# v1_5_GPS.net
KiCad netlist of a schematic drawn in Altium Designer
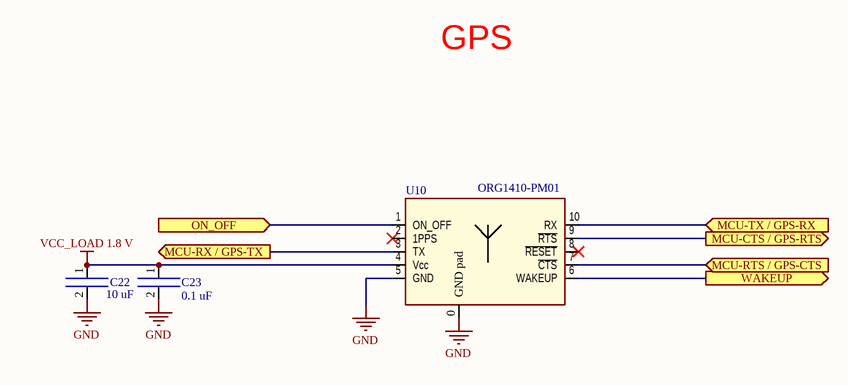
[diagram p0: v1.5 GPS.SchDoc]

(export (version "E")
  (design (tool "Eeschema 10.0.6"))
  (components
    (comp (ref "C22")
      (value "10 uF")
      (footprint "Ungravity Library:0603")
      (libsource (lib "Ungravity Library") (part "Capasistor"))
    )
    (comp (ref "C23")
      (value "0.1 uF")
      (footprint "Ungravity Library:0402")
      (libsource (lib "Ungravity Library") (part "Capasistor"))
    )
    (comp (ref "U10")
      (value "ORG1410-PM01")
      (footprint "Ungravity Library:ORG1410-PM01")
      (libsource (lib "Ungravity Library") (part "ORG1410-PM01"))
    )
  )
  (nets
    (net (code "1") (name "/MCU-CTS {slash} GPS-RTS") (class "Default")
      (node (ref "U10") (pin "9") (pinfunction "~{RTS}_9") (pintype "passive"))
    )
    (net (code "2") (name "/MCU-RTS {slash} GPS-CTS") (class "Default")
      (node (ref "U10") (pin "7") (pinfunction "~{CTS}_7") (pintype "passive"))
    )
    (net (code "3") (name "/MCU-RX {slash} GPS-TX") (class "Default")
      (node (ref "U10") (pin "3") (pinfunction "TX_3") (pintype "passive"))
    )
    (net (code "4") (name "/MCU-TX {slash} GPS-RX") (class "Default")
      (node (ref "U10") (pin "10") (pinfunction "RX_10") (pintype "passive"))
    )
    (net (code "5") (name "/ON_OFF") (class "Default")
      (node (ref "U10") (pin "1") (pinfunction "ON_OFF_1") (pintype "passive"))
    )
    (net (code "6") (name "/WAKEUP") (class "Default")
      (node (ref "U10") (pin "6") (pinfunction "WAKEUP_6") (pintype "passive"))
    )
    (net (code "7") (name "GND") (class "Default")
      (node (ref "C22") (pin "2") (pinfunction "2_2") (pintype "passive"))
      (node (ref "C23") (pin "2") (pinfunction "2_2") (pintype "passive"))
      (node (ref "U10") (pin "0") (pinfunction "GND_pad_0") (pintype "passive"))
      (node (ref "U10") (pin "5") (pinfunction "GND_5") (pintype "passive"))
    )
    (net (code "8") (name "VCC_LOAD 1.8 V") (class "Default")
      (node (ref "C22") (pin "1") (pinfunction "1_1") (pintype "passive"))
      (node (ref "C23") (pin "1") (pinfunction "1_1") (pintype "passive"))
      (node (ref "U10") (pin "4") (pinfunction "Vcc_4") (pintype "passive"))
    )
    (net (code "9") (name "unconnected-(U10-1PPS-Pad2)") (class "Default")
      (node (ref "U10") (pin "2") (pinfunction "1PPS_2") (pintype "passive+no_connect"))
    )
    (net (code "10") (name "unconnected-(U10-~{RESET}-Pad8)") (class "Default")
      (node (ref "U10") (pin "8") (pinfunction "~{RESET}_8") (pintype "passive+no_connect"))
    )
  )
)
